# RS232_NPN_PNP_FTDI_PowerSel.net
KiCad netlist of a schematic drawn in EAGLE
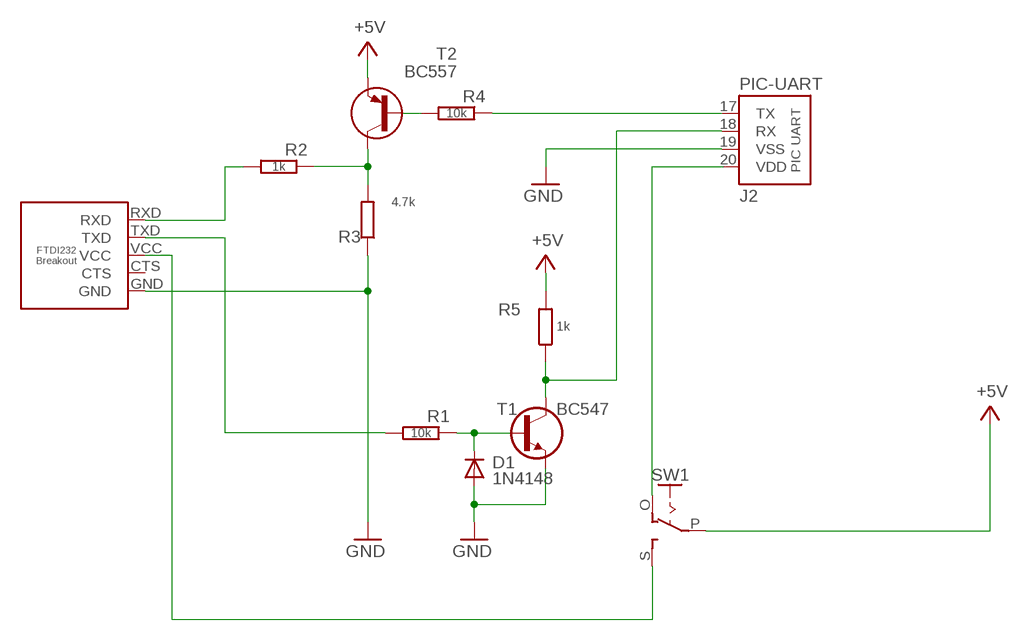
[diagram p0: schematic, sheet 1]

(export (version "E")
  (design (tool "Eeschema 10.0.6"))
  (components
    (comp (ref "D1")
      (value "1N4148")
      (footprint "eagle-import:DO34-5")
      (libsource (lib "eagle-import") (part "1N414834-5"))
    )
    (comp (ref "J1")
      (value "FTDI232-BO-5P-L")
      (footprint "eagle-import:FTDI232-BO-5-L")
      (libsource (lib "eagle-import") (part "FTDI232-BO-5P-L"))
    )
    (comp (ref "J2")
      (value "PIC-UART")
      (footprint "eagle-import:PIC-UART")
      (libsource (lib "eagle-import") (part "PIC-UART"))
    )
    (comp (ref "R1")
      (value "10k")
      (footprint "eagle-import:0202_5-V")
      (libsource (lib "eagle-import") (part "R0202/5-V"))
    )
    (comp (ref "R2")
      (value "1k")
      (footprint "eagle-import:0202_5")
      (libsource (lib "eagle-import") (part "R0202/5"))
    )
    (comp (ref "R3")
      (value "4.7k")
      (footprint "eagle-import:0202_5-V")
      (libsource (lib "eagle-import") (part "R0202/5-V"))
    )
    (comp (ref "R4")
      (value "10k")
      (footprint "eagle-import:0202_5")
      (libsource (lib "eagle-import") (part "R0202/5"))
    )
    (comp (ref "R5")
      (value "1k")
      (footprint "eagle-import:0202_5-V")
      (libsource (lib "eagle-import") (part "R0202/5-V"))
    )
    (comp (ref "SW1")
      (value "SL-SW-1P-2T-JPSW")
      (footprint "eagle-import:JPSW-1P2T")
      (libsource (lib "eagle-import") (part "SL-SW-1P-2T-JPSW"))
    )
    (comp (ref "T1")
      (value "BC547")
      (footprint "eagle-import:TO92-CBE")
      (libsource (lib "eagle-import") (part "BC547CBE"))
    )
    (comp (ref "T2")
      (value "BC557")
      (footprint "eagle-import:TO92-CBE")
      (libsource (lib "eagle-import") (part "BC557CBE"))
    )
  )
  (nets
    (net (code "1") (name "+5V") (class "Default")
      (node (ref "R5") (pin "2") (pinfunction "2_2") (pintype "passive"))
      (node (ref "SW1") (pin "P") (pinfunction "P_P") (pintype "passive"))
      (node (ref "T2") (pin "E") (pinfunction "E_E") (pintype "passive"))
    )
    (net (code "2") (name "GND") (class "Default")
      (node (ref "D1") (pin "A") (pinfunction "A_A") (pintype "passive"))
      (node (ref "J1") (pin "GND") (pinfunction "GND_GND") (pintype "bidirectional"))
      (node (ref "J2") (pin "19") (pinfunction "VSS_19") (pintype "passive"))
      (node (ref "R3") (pin "1") (pinfunction "1_1") (pintype "passive"))
      (node (ref "T1") (pin "E") (pinfunction "E_E") (pintype "passive"))
    )
    (net (code "3") (name "Net-(D1-PadC)") (class "Default")
      (node (ref "D1") (pin "C") (pinfunction "C_C") (pintype "passive"))
      (node (ref "R1") (pin "1") (pinfunction "1_1") (pintype "passive"))
      (node (ref "T1") (pin "B") (pinfunction "B_B") (pintype "passive"))
    )
    (net (code "4") (name "Net-(J1-PadRXD)") (class "Default")
      (node (ref "J1") (pin "RXD") (pinfunction "RXD_RXD") (pintype "bidirectional"))
      (node (ref "R2") (pin "2") (pinfunction "2_2") (pintype "passive"))
    )
    (net (code "5") (name "Net-(J1-PadTXD)") (class "Default")
      (node (ref "J1") (pin "TXD") (pinfunction "TXD_TXD") (pintype "bidirectional"))
      (node (ref "R1") (pin "2") (pinfunction "2_2") (pintype "passive"))
    )
    (net (code "6") (name "Net-(J1-PadVCC)") (class "Default")
      (node (ref "J1") (pin "VCC") (pinfunction "VCC_VCC") (pintype "bidirectional"))
      (node (ref "SW1") (pin "S") (pinfunction "S_S") (pintype "passive"))
    )
    (net (code "7") (name "Net-(J2-RX)") (class "Default")
      (node (ref "J2") (pin "18") (pinfunction "RX_18") (pintype "passive"))
      (node (ref "R5") (pin "1") (pinfunction "1_1") (pintype "passive"))
      (node (ref "T1") (pin "C") (pinfunction "C_C") (pintype "passive"))
    )
    (net (code "8") (name "Net-(J2-TX)") (class "Default")
      (node (ref "J2") (pin "17") (pinfunction "TX_17") (pintype "passive"))
      (node (ref "R4") (pin "1") (pinfunction "1_1") (pintype "passive"))
    )
    (net (code "9") (name "Net-(J2-VDD)") (class "Default")
      (node (ref "J2") (pin "20") (pinfunction "VDD_20") (pintype "passive"))
      (node (ref "SW1") (pin "O") (pinfunction "O_O") (pintype "passive"))
    )
    (net (code "10") (name "Net-(R2-Pad1)") (class "Default")
      (node (ref "R2") (pin "1") (pinfunction "1_1") (pintype "passive"))
      (node (ref "R3") (pin "2") (pinfunction "2_2") (pintype "passive"))
      (node (ref "T2") (pin "C") (pinfunction "C_C") (pintype "passive"))
    )
    (net (code "11") (name "Net-(R4-Pad2)") (class "Default")
      (node (ref "R4") (pin "2") (pinfunction "2_2") (pintype "passive"))
      (node (ref "T2") (pin "B") (pinfunction "B_B") (pintype "passive"))
    )
    (net (code "12") (name "unconnected-(J1-PadCTS)") (class "Default")
      (node (ref "J1") (pin "CTS") (pinfunction "CTS_CTS") (pintype "bidirectional"))
    )
  )
)
